# STSPIN32F0A_3-ph_BLDC_Motor_Driver.net
KiCad netlist of a schematic drawn in Altium Designer
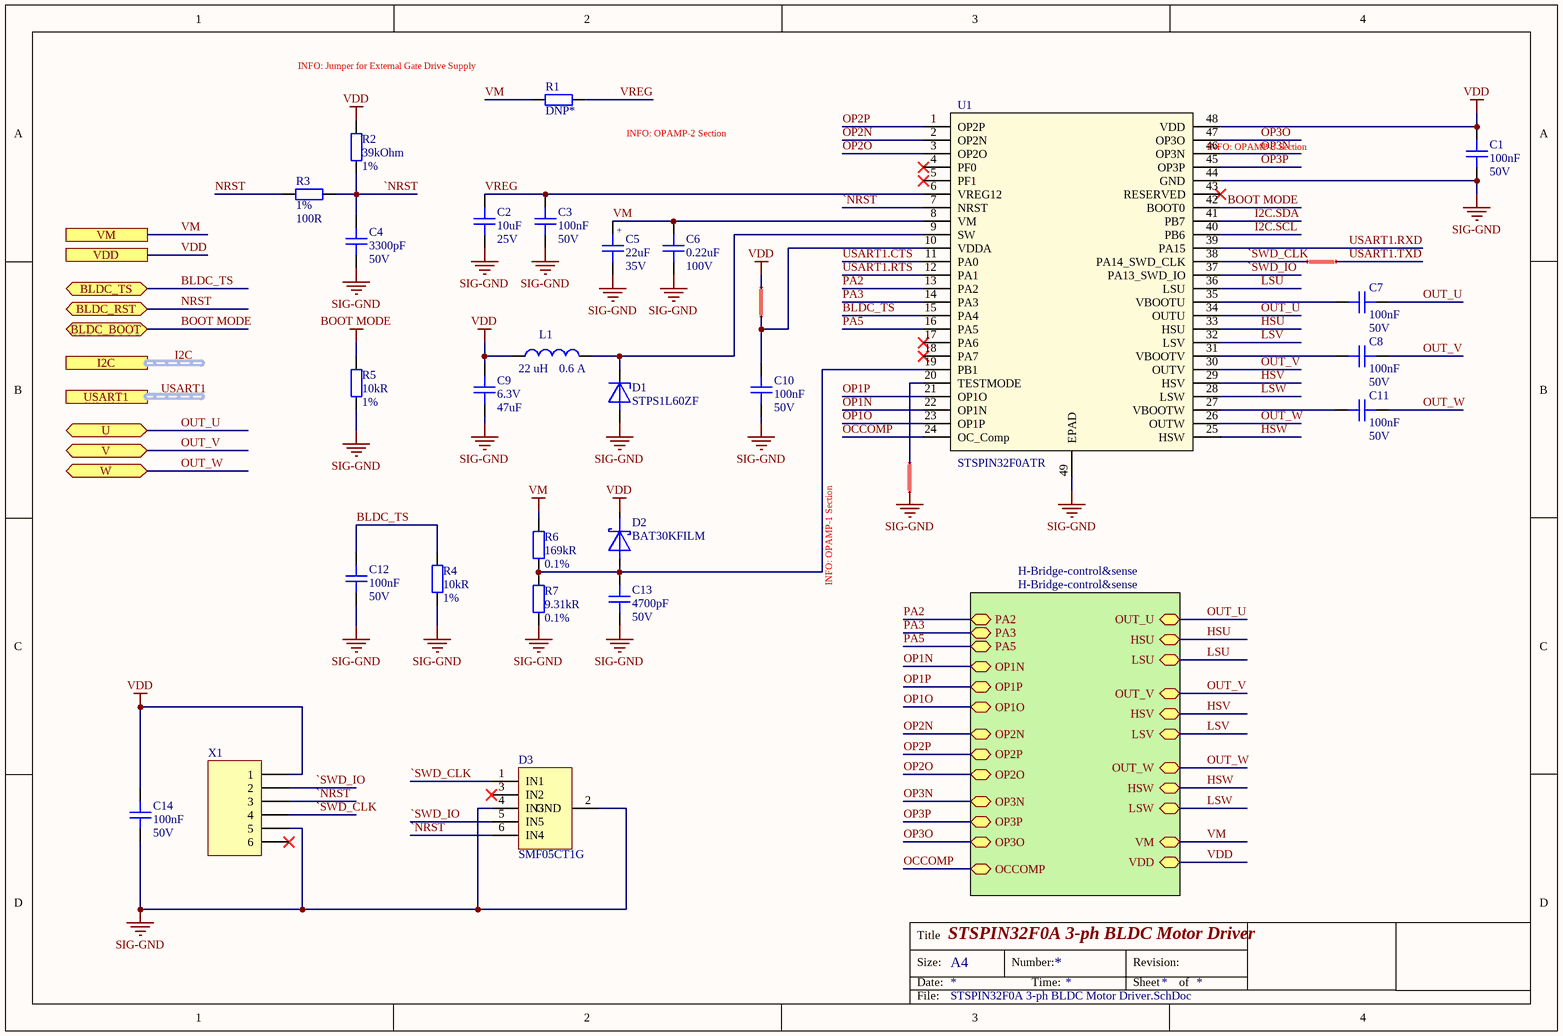
[diagram p0: STSPIN32F0A 3-ph BLDC Motor Driver.SchDoc]

(export (version "E")
  (design (tool "Eeschema 10.0.6"))
  (components
    (comp (ref "C1")
      (value "CAP CER 0.1UF 50V X7R 0402")
      (footprint "C0402")
      (description "0.1µF ±10% 50V Ceramic Capacitor X7R 0402 (1005 Metric)")
      (fields
        (field (name "MANUFACTURER") "TDK")
        (field (name "MANUFACTURER PART NUMBER") "CGA2B3X7R1H104K050BB")
        (field (name "CAPACITANCE") "100nF")
        (field (name "VOLTAGE") "50V")
      )
      (libsource (lib "capacitors_smd") (part "CAP CER 0.1UF 50V X7R 0402"))
    )
    (comp (ref "C2")
      (value "CAP CER 10UF 25V X7R 1206")
      (footprint "C1206")
      (description "10µF ±10% 25V Ceramic Capacitor X7R 1206 (3216 Metric)")
      (fields
        (field (name "MANUFACTURER") "Yageo")
        (field (name "MANUFACTURER PART NUMBER") "CC1206KKX7R8BB106")
        (field (name "CAPACITANCE") "10uF")
        (field (name "VOLTAGE RATING") "25V")
      )
      (libsource (lib "Control_Board_Model") (part "CAP CER 10UF 25V X7R 1206"))
    )
    (comp (ref "C3")
      (value "CAP CER 0.1UF 50V X7R 0402")
      (footprint "C0402")
      (description "0.1µF ±10% 50V Ceramic Capacitor X7R 0402 (1005 Metric)")
      (fields
        (field (name "MANUFACTURER") "TDK")
        (field (name "MANUFACTURER PART NUMBER") "CGA2B3X7R1H104K050BB")
        (field (name "CAPACITANCE") "100nF")
        (field (name "VOLTAGE") "50V")
      )
      (libsource (lib "capacitors_smd") (part "CAP CER 0.1UF 50V X7R 0402"))
    )
    (comp (ref "C4")
      (value "CAP CER 0402 3.3NF 50V X7R 10%")
      (footprint "C0402")
      (description "3300 pF ±10% 50V Ceramic Capacitor X7R 0402 (1005 Metric)")
      (fields
        (field (name "MANUFACTURER") "KEMET")
        (field (name "MANUFACTURER PART NUMBER") "C0402C332K5RECAUTO")
        (field (name "CAPACITANCE") "3300pF")
        (field (name "VOLTAGE RATING") "50V")
      )
      (libsource (lib "Control_Board_Model") (part "CAP CER 0402 3.3NF 50V X7R 10%"))
    )
    (comp (ref "C5")
      (value "CAP TANT 22UF 10% 35V 2917")
      (footprint "CT7343")
      (description "22 µF Molded Tantalum Capacitors 35 V 2917 (7343 Metric) 700mOhm")
      (fields
        (field (name "MANUFACTURER") "KEMET")
        (field (name "MANUFACTURER PART NUMBER") "T491X226K035AT")
        (field (name "CAPACITANCE") "22uF")
        (field (name "RATED VOLTAGE") "35V")
      )
      (libsource (lib "Control_Board_Model") (part "CAP TANT 22UF 10% 35V 2917"))
    )
    (comp (ref "C6")
      (value "CAP CER 220NF 100V X7R 0805")
      (footprint "C0805")
      (description "0.22 µF ±10% 100V Ceramic Capacitor X7R 0805 (2012 Metric)")
      (fields
        (field (name "MANUFACTURER") "KEMET")
        (field (name "MANUFACTURER PART NUMBER") "C0805C224K1RECAUTO")
        (field (name "CAPACITANCE") "0.22uF")
        (field (name "VOLTAGE RATING") "100V")
      )
      (libsource (lib "Control_Board_Model") (part "CAP CER 220NF 100V X7R 0805"))
    )
    (comp (ref "C7")
      (value "CAP CER 0.1UF 50V X7R 0402")
      (footprint "C0402")
      (description "0.1µF ±10% 50V Ceramic Capacitor X7R 0402 (1005 Metric)")
      (fields
        (field (name "MANUFACTURER") "TDK")
        (field (name "MANUFACTURER PART NUMBER") "CGA2B3X7R1H104K050BB")
        (field (name "CAPACITANCE") "100nF")
        (field (name "VOLTAGE") "50V")
      )
      (libsource (lib "capacitors_smd") (part "CAP CER 0.1UF 50V X7R 0402"))
    )
    (comp (ref "C8")
      (value "CAP CER 0.1UF 50V X7R 0402")
      (footprint "C0402")
      (description "0.1µF ±10% 50V Ceramic Capacitor X7R 0402 (1005 Metric)")
      (fields
        (field (name "MANUFACTURER") "TDK")
        (field (name "MANUFACTURER PART NUMBER") "CGA2B3X7R1H104K050BB")
        (field (name "CAPACITANCE") "100nF")
        (field (name "VOLTAGE") "50V")
      )
      (libsource (lib "capacitors_smd") (part "CAP CER 0.1UF 50V X7R 0402"))
    )
    (comp (ref "C9")
      (value "CAP CER 47UF 6.3V X5R 0603")
      (footprint "C0603")
      (description "47 µF ±20% 6.3V Ceramic Capacitor X5R 0603 (1608 Metric)")
      (fields
        (field (name "MANUFACTURER") "AVX Corporation")
        (field (name "MANUFACTURER PART NUMBER") "06036D476MAT2A")
        (field (name "VOLTAGE RATING") "6.3V")
        (field (name "CAPACITANCE") "47uF")
      )
      (libsource (lib "Control_Board_Model") (part "CAP CER 47UF 6.3V X5R 0603"))
    )
    (comp (ref "C10")
      (value "CAP CER 0.1UF 50V X7R 0402")
      (footprint "C0402")
      (description "0.1µF ±10% 50V Ceramic Capacitor X7R 0402 (1005 Metric)")
      (fields
        (field (name "MANUFACTURER") "TDK")
        (field (name "MANUFACTURER PART NUMBER") "CGA2B3X7R1H104K050BB")
        (field (name "CAPACITANCE") "100nF")
        (field (name "VOLTAGE") "50V")
      )
      (libsource (lib "capacitors_smd") (part "CAP CER 0.1UF 50V X7R 0402"))
    )
    (comp (ref "C11")
      (value "CAP CER 0.1UF 50V X7R 0402")
      (footprint "C0402")
      (description "0.1µF ±10% 50V Ceramic Capacitor X7R 0402 (1005 Metric)")
      (fields
        (field (name "MANUFACTURER") "TDK")
        (field (name "MANUFACTURER PART NUMBER") "CGA2B3X7R1H104K050BB")
        (field (name "CAPACITANCE") "100nF")
        (field (name "VOLTAGE") "50V")
      )
      (libsource (lib "capacitors_smd") (part "CAP CER 0.1UF 50V X7R 0402"))
    )
    (comp (ref "C12")
      (value "CAP CER 0.1UF 50V X7R 0402")
      (footprint "C0402")
      (description "0.1µF ±10% 50V Ceramic Capacitor X7R 0402 (1005 Metric)")
      (fields
        (field (name "MANUFACTURER") "TDK")
        (field (name "MANUFACTURER PART NUMBER") "CGA2B3X7R1H104K050BB")
        (field (name "CAPACITANCE") "100nF")
        (field (name "VOLTAGE") "50V")
      )
      (libsource (lib "capacitors_smd") (part "CAP CER 0.1UF 50V X7R 0402"))
    )
    (comp (ref "C13")
      (value "CAP CER 0402 4.7NF 50V X7R 10%")
      (footprint "C0402")
      (description "4700 pF ±10% 50V Ceramic Capacitor X7R 0402 (1005 Metric)")
      (fields
        (field (name "MANUFACTURER") "KEMET")
        (field (name "MANUFACTURER PART NUMBER") "C0402C472K5RECAUTO")
        (field (name "CAPACITANCE") "4700pF")
        (field (name "VOLTAGE RATING") "50V")
      )
      (libsource (lib "Control_Board_Model") (part "CAP CER 0402 4.7NF 50V X7R 10%"))
    )
    (comp (ref "C14")
      (value "CAP CER 0.1UF 50V X7R 0402")
      (footprint "C0402")
      (description "0.1µF ±10% 50V Ceramic Capacitor X7R 0402 (1005 Metric)")
      (fields
        (field (name "MANUFACTURER") "TDK")
        (field (name "MANUFACTURER PART NUMBER") "CGA2B3X7R1H104K050BB")
        (field (name "CAPACITANCE") "100nF")
        (field (name "VOLTAGE") "50V")
      )
      (libsource (lib "capacitors_smd") (part "CAP CER 0.1UF 50V X7R 0402"))
    )
    (comp (ref "D1")
      (value "STPS1L60ZF")
      (footprint "SOD-123FL")
      (description "Diode Schottky 60 V 1A Surface Mount SOD-123F")
      (fields (field (name "MANUFACTURER") "STMicroelectronics"))
      (libsource (lib "Control_Board_Model") (part "DIODE SCHOTTKY 60V 1A SOD123F"))
    )
    (comp (ref "D2")
      (value "BAT30KFILM")
      (footprint "SOD-523")
      (description "Diode Schottky 30 V 300mA (DC) Surface Mount SOD-523")
      (fields (field (name "MANUFACTURER") "STMicroelectronics"))
      (libsource (lib "Control_Board_Model") (part "DIODE SCHOTTKY 30V 300MA SOD523"))
    )
    (comp (ref "D3")
      (value "SMF05CT1G")
      (footprint "SOT363_SOP65P210X265-6N")
      (description "12.5V Clamp 8A (8/20µs) Ipp Tvs Diode Surface Mount SC-88/SC70-6/SOT-363")
      (fields (field (name "MANUFACTURER") "ON Semiconductor"))
      (libsource (lib "diodes_tvs") (part "TVS DIODE 5V 12.5V 5CH SC88"))
    )
    (comp (ref "J1")
      (value "Net Tie")
      (footprint "Net Tie 6x30mil")
      (libsource (lib "BLDC_Motor_Driver") (part "Net Tie Line"))
    )
    (comp (ref "J2")
      (value "Net Tie")
      (footprint "Net Tie 6x30mil")
      (libsource (lib "") (part "Net Tie Line_1"))
    )
    (comp (ref "J3")
      (value "Net Tie")
      (footprint "Net Tie 6x30mil")
      (libsource (lib "") (part "Net Tie Line_1"))
    )
    (comp (ref "L1")
      (value "FIXED IND 22UH 600MA 450MOHM SMD")
      (footprint "IND_WE_LQSH_3015")
      (description "22 µH Semi-Shielded Wirewound Inductor 600 mA 450mOhm Nonstandard")
      (fields
        (field (name "MANUFACTURER") "Wurth Elektronik")
        (field (name "MANUFACTURER PART NUMBER") "74405031010")
        (field (name "INDUCTANCE") "22 uH")
        (field (name "MAXIMUM DC CURRENT") "0.6 A")
      )
      (libsource (lib "Control_Board_Model") (part "FIXED IND 22UH 600MA 450MOHM SMD"))
    )
    (comp (ref "R1")
      (value "DNP*")
      (footprint "R0402")
      (description "Placeholder for a 0402 resistor")
      (libsource (lib "Control_Board_Model") (part "RES SMD NO BOM 0402"))
    )
    (comp (ref "R2")
      (value "RES SMD 39K OHM 1% 1/16W 0402")
      (footprint "R0402")
      (description "39 kOhms ±1% 0.063W, 1/16W Chip Resistor 0402 (1005 Metric) Moisture Resistant Thick Film")
      (fields
        (field (name "MANUFACTURER PART NUMBER") "RC0402FR-0739KL")
        (field (name "MANUFACTURER") "Yageo")
        (field (name "RESISTANCE") "39kOhm")
        (field (name "TOLERANCE") "1%")
      )
      (libsource (lib "Control_Board_Model") (part "RES SMD 39K OHM 1% 1/16W 0402"))
    )
    (comp (ref "R3")
      (value "RES SMD 100 OHM 1% 1/16W 0402")
      (footprint "R0402")
      (description "100 Ohms ±1% 0.063W, 1/16W Chip Resistor 0402 (1005 Metric) Moisture Resistant Thick Film")
      (fields
        (field (name "MANUFACTURER") "Yageo")
        (field (name "MANUFACTURER PART NUMBER") "RC0402FR-07100RL")
        (field (name "TOLERANCE") "1%")
        (field (name "RESISTANCE") "100R")
      )
      (libsource (lib "Control_Board_Model") (part "RES SMD 100 OHM 1% 1/16W 0402"))
    )
    (comp (ref "R4")
      (value "RES SMD 10K OHM 1% 1/16W 0402")
      (footprint "R0402")
      (description "10 kOhms ±1% 0.063W, 1/16W Chip Resistor 0402 (1005 Metric) Moisture Resistant Thick Film")
      (fields
        (field (name "MANUFACTURER") "Yageo")
        (field (name "MANUFACTURER PART NUMBER") "RC0402FR-0710KP")
        (field (name "RESISTANCE") "10kR")
        (field (name "TOLERANCE") "1%")
      )
      (libsource (lib "Control_Board_Model") (part "RES SMD 10K OHM 1% 1/16W 0402"))
    )
    (comp (ref "R5")
      (value "RES SMD 10K OHM 1% 1/16W 0402")
      (footprint "R0402")
      (description "10 kOhms ±1% 0.063W, 1/16W Chip Resistor 0402 (1005 Metric) Moisture Resistant Thick Film")
      (fields
        (field (name "MANUFACTURER") "Yageo")
        (field (name "MANUFACTURER PART NUMBER") "RC0402FR-0710KP")
        (field (name "RESISTANCE") "10kR")
        (field (name "TOLERANCE") "1%")
      )
      (libsource (lib "Control_Board_Model") (part "RES SMD 10K OHM 1% 1/16W 0402"))
    )
    (comp (ref "R6")
      (value "RES 169K OHM 0.1% 1/8W 0603")
      (footprint "R0603")
      (fields
        (field (name "MANUFACTURER PART NUMBER") "TNPW0603169KBEEA")
        (field (name "MANUFACTURER") "Vishay Dale")
        (field (name "RESISTANCE") "169kR")
        (field (name "TOLERANCE") "0.1%")
      )
      (libsource (lib "Control_Board_Model") (part "RES 169K OHM 0.1% 1/8W 0603"))
    )
    (comp (ref "R7")
      (value "RES SMD 9.31KOHM 0.1% 1/10W 0603")
      (footprint "R0603")
      (fields
        (field (name "MANUFACTURER PART NUMBER") "RG1608P-9311-B-T5")
        (field (name "MANUFACTURER") "Susumu")
        (field (name "RESISTANCE") "9.31kR")
        (field (name "TOLERANCE") "0.1%")
      )
      (libsource (lib "Control_Board_Model") (part "RES SMD 9.31KOHM 0.1% 1/10W 0603"))
    )
    (comp (ref "U1")
      (value "STSPIN32F0ATR")
      (footprint "VFQFPN-48")
      (description "Multiphase Motor Driver Power MOSFET Analog, I²C, PWM 48VFQFPN")
      (fields (field (name "MANUFACTURER") "STMicroelectronics"))
      (libsource (lib "Control_Board_Model") (part "IC BLDC CTLR STM32 48VFQFPN"))
    )
    (comp (ref "X1")
      (value "~")
      (footprint "TC2030-IDC-NL")
      (description "Tag-Connect TC2030-MCP-NL (3x2 pins No Legs)")
      (fields
        (field (name "MANUFACTURER") "Tag-Connect LLC")
        (field (name "MANUFACTURER PART NUMBER") "TC2030-IDC-NL")
      )
      (libsource (lib "EvansWerks") (part "TC2030-IDC-NL"))
    )
  )
  (nets
    (net (code "3") (name "/BLDC_TS") (class "Default")
      (node (ref "C12") (pin "2") (pinfunction "2_2") (pintype "passive"))
      (node (ref "R4") (pin "1") (pinfunction "1_1") (pintype "passive"))
      (node (ref "U1") (pin "15") (pinfunction "PA4_15") (pintype "passive"))
    )
    (net (code "4") (name "/HSU") (class "Default")
      (node (ref "U1") (pin "33") (pinfunction "HSU_33") (pintype "passive"))
    )
    (net (code "5") (name "/HSV") (class "Default")
      (node (ref "U1") (pin "29") (pinfunction "HSV_29") (pintype "passive"))
    )
    (net (code "6") (name "/HSW") (class "Default")
      (node (ref "U1") (pin "25") (pinfunction "HSW_25") (pintype "passive"))
    )
    (net (code "7") (name "/I2C.SCL") (class "Default")
      (node (ref "U1") (pin "40") (pinfunction "PB6_40") (pintype "passive"))
    )
    (net (code "8") (name "/I2C.SDA") (class "Default")
      (node (ref "U1") (pin "41") (pinfunction "PB7_41") (pintype "passive"))
    )
    (net (code "9") (name "/LSU") (class "Default")
      (node (ref "U1") (pin "36") (pinfunction "LSU_36") (pintype "passive"))
    )
    (net (code "10") (name "/LSV") (class "Default")
      (node (ref "U1") (pin "32") (pinfunction "LSV_32") (pintype "passive"))
    )
    (net (code "11") (name "/LSW") (class "Default")
      (node (ref "U1") (pin "28") (pinfunction "LSW_28") (pintype "passive"))
    )
    (net (code "12") (name "/NRST") (class "Default")
      (node (ref "R3") (pin "2") (pinfunction "2_2") (pintype "passive"))
    )
    (net (code "13") (name "/OCCOMP") (class "Default")
      (node (ref "U1") (pin "24") (pinfunction "OC_Comp_24") (pintype "passive"))
    )
    (net (code "14") (name "/OP1N") (class "Default")
      (node (ref "U1") (pin "22") (pinfunction "OP1N_22") (pintype "passive"))
    )
    (net (code "15") (name "/OP1O") (class "Default")
      (node (ref "U1") (pin "23") (pinfunction "OP1P_23") (pintype "passive"))
    )
    (net (code "16") (name "/OP1P") (class "Default")
      (node (ref "U1") (pin "21") (pinfunction "OP1O_21") (pintype "passive"))
    )
    (net (code "17") (name "/OP2N") (class "Default")
      (node (ref "U1") (pin "2") (pinfunction "OP2N_2") (pintype "passive"))
    )
    (net (code "18") (name "/OP2O") (class "Default")
      (node (ref "U1") (pin "3") (pinfunction "OP2O_3") (pintype "passive"))
    )
    (net (code "19") (name "/OP2P") (class "Default")
      (node (ref "U1") (pin "1") (pinfunction "OP2P_1") (pintype "passive"))
    )
    (net (code "20") (name "/OP3N") (class "Default")
      (node (ref "U1") (pin "46") (pinfunction "OP3N_46") (pintype "passive"))
    )
    (net (code "21") (name "/OP3O") (class "Default")
      (node (ref "U1") (pin "47") (pinfunction "OP3O_47") (pintype "passive"))
    )
    (net (code "22") (name "/OP3P") (class "Default")
      (node (ref "U1") (pin "45") (pinfunction "OP3P_45") (pintype "passive"))
    )
    (net (code "23") (name "/OUT_U") (class "Default")
      (node (ref "C7") (pin "2") (pinfunction "2_2") (pintype "passive"))
      (node (ref "U1") (pin "34") (pinfunction "OUTU_34") (pintype "passive"))
    )
    (net (code "24") (name "/OUT_V") (class "Default")
      (node (ref "C8") (pin "2") (pinfunction "2_2") (pintype "passive"))
      (node (ref "U1") (pin "30") (pinfunction "OUTV_30") (pintype "passive"))
    )
    (net (code "25") (name "/OUT_W") (class "Default")
      (node (ref "C11") (pin "2") (pinfunction "2_2") (pintype "passive"))
      (node (ref "U1") (pin "26") (pinfunction "OUTW_26") (pintype "passive"))
    )
    (net (code "26") (name "/PA2") (class "Default")
      (node (ref "U1") (pin "13") (pinfunction "PA2_13") (pintype "passive"))
    )
    (net (code "27") (name "/PA3") (class "Default")
      (node (ref "U1") (pin "14") (pinfunction "PA3_14") (pintype "passive"))
    )
    (net (code "28") (name "/PA5") (class "Default")
      (node (ref "U1") (pin "16") (pinfunction "PA5_16") (pintype "passive"))
    )
    (net (code "29") (name "/USART1.CTS") (class "Default")
      (node (ref "U1") (pin "11") (pinfunction "PA0_11") (pintype "passive"))
    )
    (net (code "30") (name "/USART1.RTS") (class "Default")
      (node (ref "U1") (pin "12") (pinfunction "PA1_12") (pintype "passive"))
    )
    (net (code "31") (name "/USART1.RXD") (class "Default")
      (node (ref "U1") (pin "39") (pinfunction "PA15_39") (pintype "passive"))
    )
    (net (code "32") (name "/USART1.TXD") (class "Default") (node (ref "J1") (pin "2") (pintype "passive")))
    (net (code "33") (name "/VREG") (class "Default")
      (node (ref "C2") (pin "2") (pinfunction "2_2") (pintype "passive"))
      (node (ref "C3") (pin "1") (pinfunction "1_1") (pintype "passive"))
      (node (ref "R1") (pin "1") (pinfunction "1_1") (pintype "passive"))
      (node (ref "U1") (pin "6") (pinfunction "VREG12_6") (pintype "passive"))
    )
    (net (code "34") (name "/`NRST") (class "Default")
      (node (ref "C4") (pin "2") (pinfunction "2_2") (pintype "passive"))
      (node (ref "D3") (pin "6") (pinfunction "IN4_6") (pintype "passive"))
      (node (ref "R2") (pin "2") (pinfunction "2_2") (pintype "passive"))
      (node (ref "R3") (pin "1") (pinfunction "1_1") (pintype "passive"))
      (node (ref "U1") (pin "7") (pinfunction "NRST_7") (pintype "passive"))
      (node (ref "X1") (pin "3") (pinfunction "3_3") (pintype "passive"))
    )
    (net (code "35") (name "/`SWD_CLK") (class "Default")
      (node (ref "D3") (pin "1") (pinfunction "IN1_1") (pintype "passive"))
      (node (ref "J1") (pin "1") (pintype "passive"))
      (node (ref "U1") (pin "38") (pinfunction "PA14_SWD_CLK_38") (pintype "passive"))
      (node (ref "X1") (pin "4") (pinfunction "4_4") (pintype "passive"))
    )
    (net (code "36") (name "/`SWD_IO") (class "Default")
      (node (ref "D3") (pin "5") (pinfunction "IN5_5") (pintype "passive"))
      (node (ref "U1") (pin "37") (pinfunction "PA13_SWD_IO_37") (pintype "passive"))
      (node (ref "X1") (pin "2") (pinfunction "2_2") (pintype "passive"))
    )
    (net (code "39") (name "BOOT MODE") (class "Default")
      (node (ref "R5") (pin "1") (pinfunction "1_1") (pintype "passive"))
      (node (ref "U1") (pin "42") (pinfunction "BOOT0_42") (pintype "passive"))
    )
    (net (code "40") (name "Net-(D1-K)") (class "Default")
      (node (ref "D1") (pin "1") (pinfunction "K_1") (pintype "passive"))
      (node (ref "L1") (pin "2") (pinfunction "2_2") (pintype "passive"))
      (node (ref "U1") (pin "9") (pinfunction "SW_9") (pintype "passive"))
    )
    (net (code "41") (name "Net-(D2-A)") (class "Default")
      (node (ref "C13") (pin "2") (pinfunction "2_2") (pintype "passive"))
      (node (ref "D2") (pin "2") (pinfunction "A_2") (pintype "passive"))
      (node (ref "R6") (pin "1") (pinfunction "1_1") (pintype "passive"))
      (node (ref "R7") (pin "2") (pinfunction "2_2") (pintype "passive"))
      (node (ref "U1") (pin "19") (pinfunction "PB1_19") (pintype "passive"))
    )
    (net (code "42") (name "Net-(U1-TESTMODE)") (class "Default")
      (node (ref "J3") (pin "2") (pintype "passive"))
      (node (ref "U1") (pin "20") (pinfunction "TESTMODE_20") (pintype "passive"))
    )
    (net (code "43") (name "Net-(U1-VBOOTU)") (class "Default")
      (node (ref "C7") (pin "1") (pinfunction "1_1") (pintype "passive"))
      (node (ref "U1") (pin "35") (pinfunction "VBOOTU_35") (pintype "passive"))
    )
    (net (code "44") (name "Net-(U1-VBOOTV)") (class "Default")
      (node (ref "C8") (pin "1") (pinfunction "1_1") (pintype "passive"))
      (node (ref "U1") (pin "31") (pinfunction "VBOOTV_31") (pintype "passive"))
    )
    (net (code "45") (name "Net-(U1-VBOOTW)") (class "Default")
      (node (ref "C11") (pin "1") (pinfunction "1_1") (pintype "passive"))
      (node (ref "U1") (pin "27") (pinfunction "VBOOTW_27") (pintype "passive"))
    )
    (net (code "46") (name "Net-(U1-VDDA)") (class "Default")
      (node (ref "C10") (pin "1") (pinfunction "1_1") (pintype "passive"))
      (node (ref "J2") (pin "1") (pintype "passive"))
      (node (ref "U1") (pin "10") (pinfunction "VDDA_10") (pintype "passive"))
    )
    (net (code "47") (name "SIG-GND") (class "Default")
      (node (ref "C1") (pin "2") (pinfunction "2_2") (pintype "passive"))
      (node (ref "C10") (pin "2") (pinfunction "2_2") (pintype "passive"))
      (node (ref "C12") (pin "1") (pinfunction "1_1") (pintype "passive"))
      (node (ref "C13") (pin "1") (pinfunction "1_1") (pintype "passive"))
      (node (ref "C14") (pin "1") (pinfunction "1_1") (pintype "passive"))
      (node (ref "C2") (pin "1") (pinfunction "1_1") (pintype "passive"))
      (node (ref "C3") (pin "2") (pinfunction "2_2") (pintype "passive"))
      (node (ref "C4") (pin "1") (pinfunction "1_1") (pintype "passive"))
      (node (ref "C5") (pin "2") (pinfunction "2_2") (pintype "passive"))
      (node (ref "C6") (pin "1") (pinfunction "1_1") (pintype "passive"))
      (node (ref "C9") (pin "1") (pinfunction "1_1") (pintype "passive"))
      (node (ref "D1") (pin "2") (pinfunction "A_2") (pintype "passive"))
      (node (ref "D3") (pin "2") (pinfunction "GND_2") (pintype "power_in"))
      (node (ref "D3") (pin "4") (pinfunction "IN3_4") (pintype "passive"))
      (node (ref "J3") (pin "1") (pintype "passive"))
      (node (ref "R4") (pin "2") (pinfunction "2_2") (pintype "passive"))
      (node (ref "R5") (pin "2") (pinfunction "2_2") (pintype "passive"))
      (node (ref "R7") (pin "1") (pinfunction "1_1") (pintype "passive"))
      (node (ref "U1") (pin "44") (pinfunction "GND_44") (pintype "passive"))
      (node (ref "U1") (pin "49") (pinfunction "EPAD_49") (pintype "passive"))
      (node (ref "X1") (pin "5") (pinfunction "5_5") (pintype "passive"))
    )
    (net (code "48") (name "VDD") (class "Default")
      (node (ref "C1") (pin "1") (pinfunction "1_1") (pintype "passive"))
      (node (ref "C14") (pin "2") (pinfunction "2_2") (pintype "passive"))
      (node (ref "C9") (pin "2") (pinfunction "2_2") (pintype "passive"))
      (node (ref "D2") (pin "1") (pinfunction "K_1") (pintype "passive"))
      (node (ref "J2") (pin "2") (pintype "passive"))
      (node (ref "L1") (pin "1") (pinfunction "1_1") (pintype "passive"))
      (node (ref "R2") (pin "1") (pinfunction "1_1") (pintype "passive"))
      (node (ref "U1") (pin "48") (pinfunction "VDD_48") (pintype "passive"))
      (node (ref "X1") (pin "1") (pinfunction "1_1") (pintype "passive"))
    )
    (net (code "49") (name "VM") (class "Default")
      (node (ref "C5") (pin "1") (pinfunction "1_1") (pintype "passive"))
      (node (ref "C6") (pin "2") (pinfunction "2_2") (pintype "passive"))
      (node (ref "R1") (pin "2") (pinfunction "2_2") (pintype "passive"))
      (node (ref "R6") (pin "2") (pinfunction "2_2") (pintype "passive"))
      (node (ref "U1") (pin "8") (pinfunction "VM_8") (pintype "passive"))
    )
    (net (code "50") (name "unconnected-(D3-IN2-Pad3)") (class "Default")
      (node (ref "D3") (pin "3") (pinfunction "IN2_3") (pintype "passive+no_connect"))
    )
    (net (code "51") (name "unconnected-(U1-PA6-Pad17)") (class "Default")
      (node (ref "U1") (pin "17") (pinfunction "PA6_17") (pintype "passive+no_connect"))
    )
    (net (code "52") (name "unconnected-(U1-PA7-Pad18)") (class "Default")
      (node (ref "U1") (pin "18") (pinfunction "PA7_18") (pintype "passive+no_connect"))
    )
    (net (code "53") (name "unconnected-(U1-PF0-Pad4)") (class "Default")
      (node (ref "U1") (pin "4") (pinfunction "PF0_4") (pintype "passive+no_connect"))
    )
    (net (code "54") (name "unconnected-(U1-PF1-Pad5)") (class "Default")
      (node (ref "U1") (pin "5") (pinfunction "PF1_5") (pintype "passive+no_connect"))
    )
    (net (code "55") (name "unconnected-(U1-RESERVED-Pad43)") (class "Default")
      (node (ref "U1") (pin "43") (pinfunction "RESERVED_43") (pintype "passive+no_connect"))
    )
    (net (code "56") (name "unconnected-(X1-Pad6)") (class "Default")
      (node (ref "X1") (pin "6") (pinfunction "6_6") (pintype "passive+no_connect"))
    )
  )
)
